# KN-CON_LCD_100.net
KiCad netlist of a schematic drawn in EAGLE
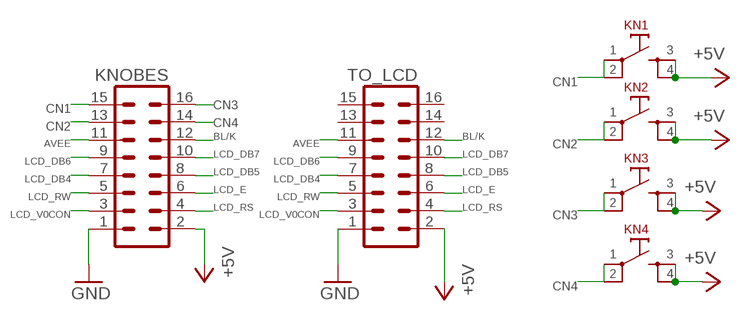
[diagram p0: schematic, sheet 1]

(export (version "E")
  (design (tool "Eeschema 10.0.6"))
  (components
    (comp (ref "KN1")
      (value "LZQ-KN")
      (footprint "eagle-import:LZQ-KN")
      (libsource (lib "eagle-import") (part "LZQ-KN"))
    )
    (comp (ref "KN2")
      (value "LZQ-KN")
      (footprint "eagle-import:LZQ-KN")
      (libsource (lib "eagle-import") (part "LZQ-KN"))
    )
    (comp (ref "KN3")
      (value "LZQ-KN")
      (footprint "eagle-import:LZQ-KN")
      (libsource (lib "eagle-import") (part "LZQ-KN"))
    )
    (comp (ref "KN4")
      (value "LZQ-KN")
      (footprint "eagle-import:LZQ-KN")
      (libsource (lib "eagle-import") (part "LZQ-KN"))
    )
    (comp (ref "KNOBES")
      (value "ML16")
      (footprint "eagle-import:ML16")
      (fields (field (name "OC_FARNELL") "unknown") (field (name "OC_NEWARK") "unknown"))
      (libsource (lib "eagle-import") (part "ML16"))
    )
    (comp (ref "TO_LCD")
      (value "ML16")
      (footprint "eagle-import:ML16")
      (fields (field (name "OC_FARNELL") "unknown") (field (name "OC_NEWARK") "unknown"))
      (libsource (lib "eagle-import") (part "ML16"))
    )
  )
  (nets
    (net (code "1") (name "+5V") (class "Default")
      (node (ref "KN1") (pin "3") (pinfunction "3_3") (pintype "bidirectional"))
      (node (ref "KN1") (pin "4") (pinfunction "4_4") (pintype "bidirectional"))
      (node (ref "KN2") (pin "3") (pinfunction "3_3") (pintype "bidirectional"))
      (node (ref "KN2") (pin "4") (pinfunction "4_4") (pintype "bidirectional"))
      (node (ref "KN3") (pin "3") (pinfunction "3_3") (pintype "bidirectional"))
      (node (ref "KN3") (pin "4") (pinfunction "4_4") (pintype "bidirectional"))
      (node (ref "KN4") (pin "3") (pinfunction "3_3") (pintype "bidirectional"))
      (node (ref "KN4") (pin "4") (pinfunction "4_4") (pintype "bidirectional"))
      (node (ref "KNOBES") (pin "2") (pinfunction "2_2") (pintype "passive"))
      (node (ref "TO_LCD") (pin "2") (pinfunction "2_2") (pintype "passive"))
    )
    (net (code "2") (name "/AVEE") (class "Default")
      (node (ref "KNOBES") (pin "11") (pinfunction "11_11") (pintype "passive"))
      (node (ref "TO_LCD") (pin "11") (pinfunction "11_11") (pintype "passive"))
    )
    (net (code "3") (name "/BL{slash}K") (class "Default")
      (node (ref "KNOBES") (pin "12") (pinfunction "12_12") (pintype "passive"))
      (node (ref "TO_LCD") (pin "12") (pinfunction "12_12") (pintype "passive"))
    )
    (net (code "4") (name "/CN1") (class "Default")
      (node (ref "KN1") (pin "1") (pinfunction "1_1") (pintype "bidirectional"))
      (node (ref "KN1") (pin "2") (pinfunction "2_2") (pintype "bidirectional"))
      (node (ref "KNOBES") (pin "15") (pinfunction "15_15") (pintype "passive"))
    )
    (net (code "5") (name "/CN2") (class "Default")
      (node (ref "KN2") (pin "1") (pinfunction "1_1") (pintype "bidirectional"))
      (node (ref "KN2") (pin "2") (pinfunction "2_2") (pintype "bidirectional"))
      (node (ref "KNOBES") (pin "13") (pinfunction "13_13") (pintype "passive"))
    )
    (net (code "6") (name "/CN3") (class "Default")
      (node (ref "KN3") (pin "1") (pinfunction "1_1") (pintype "bidirectional"))
      (node (ref "KN3") (pin "2") (pinfunction "2_2") (pintype "bidirectional"))
      (node (ref "KNOBES") (pin "16") (pinfunction "16_16") (pintype "passive"))
    )
    (net (code "7") (name "/CN4") (class "Default")
      (node (ref "KN4") (pin "1") (pinfunction "1_1") (pintype "bidirectional"))
      (node (ref "KN4") (pin "2") (pinfunction "2_2") (pintype "bidirectional"))
      (node (ref "KNOBES") (pin "14") (pinfunction "14_14") (pintype "passive"))
    )
    (net (code "8") (name "/LCD_DB4") (class "Default")
      (node (ref "KNOBES") (pin "7") (pinfunction "7_7") (pintype "passive"))
      (node (ref "TO_LCD") (pin "7") (pinfunction "7_7") (pintype "passive"))
    )
    (net (code "9") (name "/LCD_DB5") (class "Default")
      (node (ref "KNOBES") (pin "8") (pinfunction "8_8") (pintype "passive"))
      (node (ref "TO_LCD") (pin "8") (pinfunction "8_8") (pintype "passive"))
    )
    (net (code "10") (name "/LCD_DB6") (class "Default")
      (node (ref "KNOBES") (pin "9") (pinfunction "9_9") (pintype "passive"))
      (node (ref "TO_LCD") (pin "9") (pinfunction "9_9") (pintype "passive"))
    )
    (net (code "11") (name "/LCD_DB7") (class "Default")
      (node (ref "KNOBES") (pin "10") (pinfunction "10_10") (pintype "passive"))
      (node (ref "TO_LCD") (pin "10") (pinfunction "10_10") (pintype "passive"))
    )
    (net (code "12") (name "/LCD_E") (class "Default")
      (node (ref "KNOBES") (pin "6") (pinfunction "6_6") (pintype "passive"))
      (node (ref "TO_LCD") (pin "6") (pinfunction "6_6") (pintype "passive"))
    )
    (net (code "13") (name "/LCD_RS") (class "Default")
      (node (ref "KNOBES") (pin "4") (pinfunction "4_4") (pintype "passive"))
      (node (ref "TO_LCD") (pin "4") (pinfunction "4_4") (pintype "passive"))
    )
    (net (code "14") (name "/LCD_RW") (class "Default")
      (node (ref "KNOBES") (pin "5") (pinfunction "5_5") (pintype "passive"))
      (node (ref "TO_LCD") (pin "5") (pinfunction "5_5") (pintype "passive"))
    )
    (net (code "15") (name "/LCD_V0CON") (class "Default")
      (node (ref "KNOBES") (pin "3") (pinfunction "3_3") (pintype "passive"))
      (node (ref "TO_LCD") (pin "3") (pinfunction "3_3") (pintype "passive"))
    )
    (net (code "16") (name "GND") (class "Default")
      (node (ref "KNOBES") (pin "1") (pinfunction "1_1") (pintype "passive"))
      (node (ref "TO_LCD") (pin "1") (pinfunction "1_1") (pintype "passive"))
    )
    (net (code "17") (name "unconnected-(TO_LCD-Pad13)") (class "Default")
      (node (ref "TO_LCD") (pin "13") (pinfunction "13_13") (pintype "passive"))
    )
    (net (code "18") (name "unconnected-(TO_LCD-Pad14)") (class "Default")
      (node (ref "TO_LCD") (pin "14") (pinfunction "14_14") (pintype "passive"))
    )
    (net (code "19") (name "unconnected-(TO_LCD-Pad15)") (class "Default")
      (node (ref "TO_LCD") (pin "15") (pinfunction "15_15") (pintype "passive"))
    )
    (net (code "20") (name "unconnected-(TO_LCD-Pad16)") (class "Default")
      (node (ref "TO_LCD") (pin "16") (pinfunction "16_16") (pintype "passive"))
    )
  )
)
